# MAX14921_AFE.net
KiCad netlist of a schematic drawn in Altium Designer
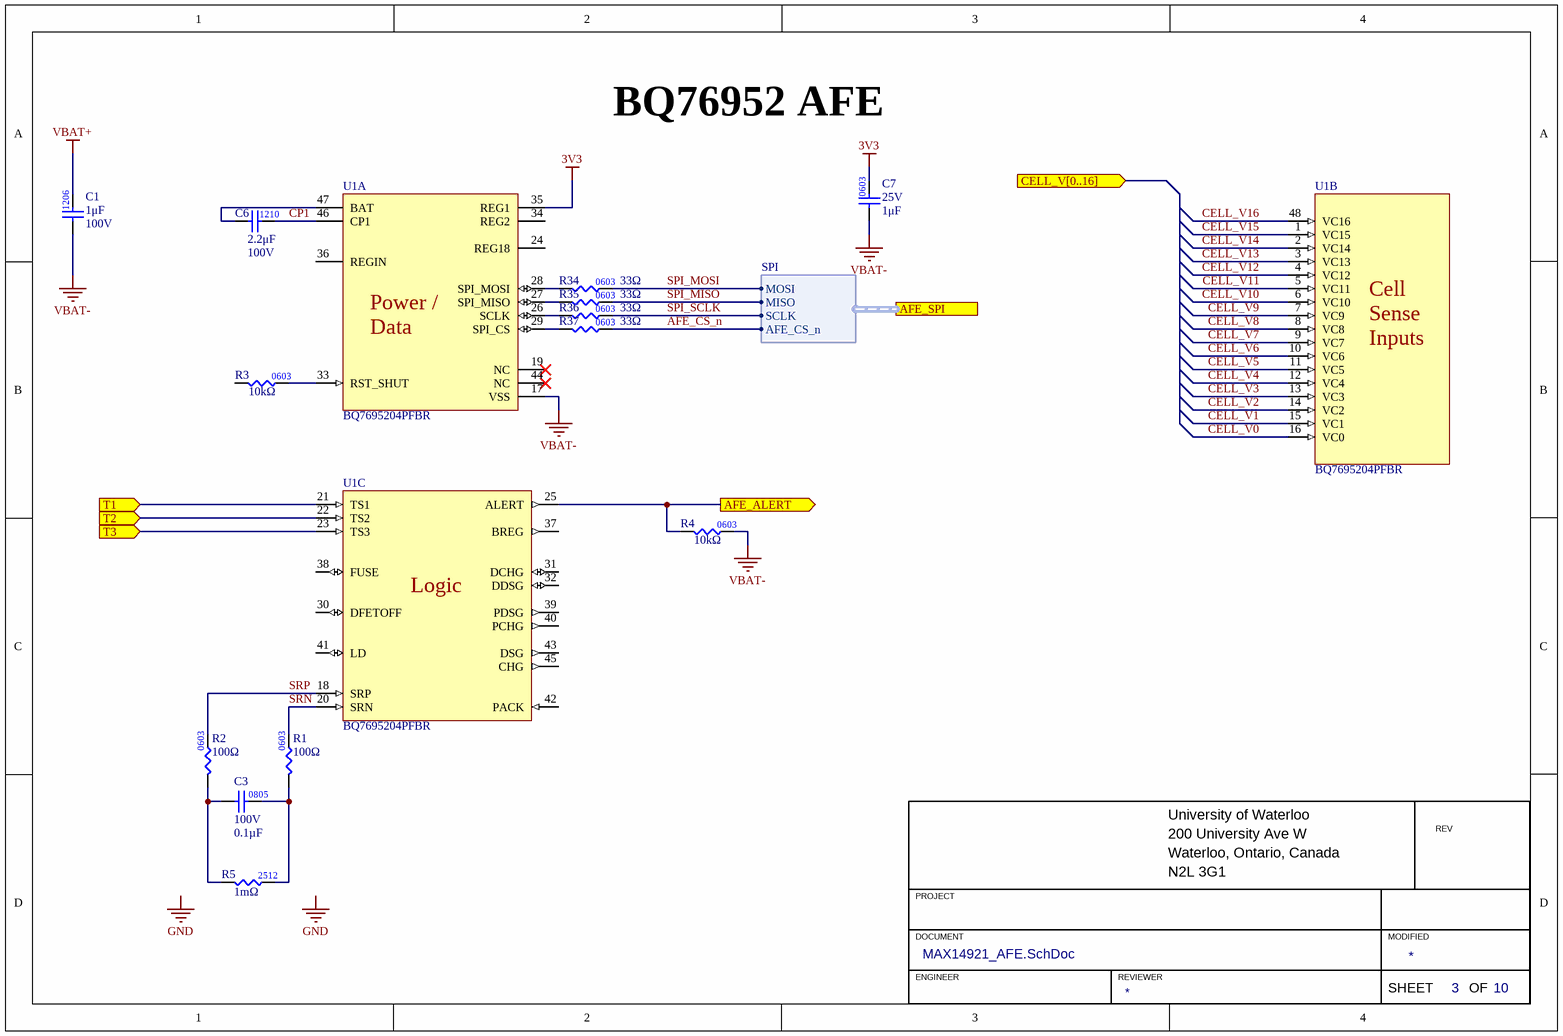
[diagram p0: MAX14921_AFE.SchDoc]

(export (version "E")
  (design (tool "Eeschema 10.0.6"))
  (components
    (comp (ref "C1")
      (value "1μF")
      (footprint "CAP1206")
      (description "CAP CER 1UF 100V X7R 1206")
      (fields (field (name "VOLTAGE RATING") "100V") (field (name "Comment") "CAP_1uF_100V_1206"))
      (libsource (lib "Personal_Schematic_Library_2022") (part "CAP_1uF_100V_1206"))
    )
    (comp (ref "C3")
      (value "0.1µF")
      (footprint "CAP0805")
      (description "CAP CER 0.1UF 100V X7R 0805")
      (fields (field (name "VOLTAGE RATING") "100V") (field (name "Comment") "CAP_0.1uF_100V_0805"))
      (libsource (lib "Personal_Schematic_Library_2022") (part "CAP_0.1uF_100V_0805"))
    )
    (comp (ref "C6")
      (value "2.2μF")
      (footprint "CAP1210")
      (description "CAP CER 2.2UF 100V X7R 1210")
      (fields (field (name "VOLTAGE RATING") "100V") (field (name "Comment") "CAP_2.2uF_100V_1210"))
      (libsource (lib "Personal_Schematic_Library_2022") (part "CAP_2.2uF_100V_1210"))
    )
    (comp (ref "C7")
      (value "1μF")
      (footprint "CAP0603")
      (description "CAP CER 1UF 25V X5R 0603")
      (fields (field (name "VOLTAGE RATING") "25V") (field (name "Comment") "CAP_1uF_25V_0603"))
      (libsource (lib "Personal_Schematic_Library_2022") (part "CAP_1uF_25V_0603"))
    )
    (comp (ref "R1")
      (value "100Ω")
      (footprint "RES0603")
      (description "RES 100 OHM 1% 1/10W 0603")
      (fields (field (name "Comment") "RES_100Ω_0603_1%"))
      (libsource (lib "Personal_Schematic_Library_2022") (part "RES_100Ω_0603_1%"))
    )
    (comp (ref "R2")
      (value "100Ω")
      (footprint "RES0603")
      (description "RES 100 OHM 1% 1/10W 0603")
      (fields (field (name "Comment") "RES_100Ω_0603_1%"))
      (libsource (lib "Personal_Schematic_Library_2022") (part "RES_100Ω_0603_1%"))
    )
    (comp (ref "R3")
      (value "10kΩ")
      (footprint "RES0603")
      (description "RES 10K OHM 1% 1/8W 0603")
      (fields (field (name "Comment") "RES_10kΩ_0603_1%"))
      (libsource (lib "Personal_Schematic_Library_2022") (part "RES_10kΩ_0603_1%"))
    )
    (comp (ref "R4")
      (value "10kΩ")
      (footprint "RES0603")
      (description "RES 10K OHM 1% 1/8W 0603")
      (fields (field (name "Comment") "RES_10kΩ_0603_1%"))
      (libsource (lib "Personal_Schematic_Library_2022") (part "RES_10kΩ_0603_1%"))
    )
    (comp (ref "R5")
      (value "1mΩ")
      (footprint "RESC6532X75N")
      (description "RES 1 mOHM 1% 3W 2512")
      (fields (field (name "Comment") "RES_1mΩ_2512_1%"))
      (libsource (lib "Personal_Schematic_Library_2022") (part "RES_1mΩ_2512_1%"))
    )
    (comp (ref "R34")
      (value "33Ω")
      (footprint "RES0603")
      (description "RES 33 OHM 1% 1/10W 0603")
      (fields (field (name "Comment") "RES_33Ω_0603_1%"))
      (libsource (lib "Personal_Schematic_Library_2022") (part "RES_33Ω_0603_1%"))
    )
    (comp (ref "R35")
      (value "33Ω")
      (footprint "RES0603")
      (description "RES 33 OHM 1% 1/10W 0603")
      (fields (field (name "Comment") "RES_33Ω_0603_1%"))
      (libsource (lib "Personal_Schematic_Library_2022") (part "RES_33Ω_0603_1%"))
    )
    (comp (ref "R36")
      (value "33Ω")
      (footprint "RES0603")
      (description "RES 33 OHM 1% 1/10W 0603")
      (fields (field (name "Comment") "RES_33Ω_0603_1%"))
      (libsource (lib "Personal_Schematic_Library_2022") (part "RES_33Ω_0603_1%"))
    )
    (comp (ref "R37")
      (value "33Ω")
      (footprint "RES0603")
      (description "RES 33 OHM 1% 1/10W 0603")
      (fields (field (name "Comment") "RES_33Ω_0603_1%"))
      (libsource (lib "Personal_Schematic_Library_2022") (part "RES_33Ω_0603_1%"))
    )
    (comp (ref "U1")
      (value "BQ7695204PFBR")
      (footprint "TI_48-TQFP")
      (description "IC BAT LIFEPO4/LI-ION 3-16C TQFP")
      (libsource (lib "Personal_Schematic_Library_2022") (part "BQ7695204PFBR"))
    )
  )
  (nets
    (net (code "2") (name "/AFE_ALERT") (class "Default")
      (node (ref "R4") (pin "1") (pinfunction "1_1") (pintype "passive"))
      (node (ref "U1") (pin "25") (pinfunction "ALERT_25") (pintype "output"))
    )
    (net (code "3") (name "/AFE_CS_n") (class "Default")
      (node (ref "R37") (pin "2") (pinfunction "2_2") (pintype "passive"))
    )
    (net (code "4") (name "/CELL_V0") (class "Default")
      (node (ref "U1") (pin "16") (pinfunction "VC0_16") (pintype "input"))
    )
    (net (code "5") (name "/CELL_V1") (class "Default")
      (node (ref "U1") (pin "15") (pinfunction "VC1_15") (pintype "input"))
    )
    (net (code "6") (name "/CELL_V2") (class "Default")
      (node (ref "U1") (pin "14") (pinfunction "VC2_14") (pintype "input"))
    )
    (net (code "7") (name "/CELL_V3") (class "Default")
      (node (ref "U1") (pin "13") (pinfunction "VC3_13") (pintype "input"))
    )
    (net (code "8") (name "/CELL_V4") (class "Default")
      (node (ref "U1") (pin "12") (pinfunction "VC4_12") (pintype "input"))
    )
    (net (code "9") (name "/CELL_V5") (class "Default")
      (node (ref "U1") (pin "11") (pinfunction "VC5_11") (pintype "input"))
    )
    (net (code "10") (name "/CELL_V6") (class "Default")
      (node (ref "U1") (pin "10") (pinfunction "VC6_10") (pintype "input"))
    )
    (net (code "11") (name "/CELL_V7") (class "Default")
      (node (ref "U1") (pin "9") (pinfunction "VC7_9") (pintype "input"))
    )
    (net (code "12") (name "/CELL_V8") (class "Default")
      (node (ref "U1") (pin "8") (pinfunction "VC8_8") (pintype "input"))
    )
    (net (code "13") (name "/CELL_V9") (class "Default")
      (node (ref "U1") (pin "7") (pinfunction "VC9_7") (pintype "input"))
    )
    (net (code "14") (name "/CELL_V10") (class "Default")
      (node (ref "U1") (pin "6") (pinfunction "VC10_6") (pintype "input"))
    )
    (net (code "15") (name "/CELL_V11") (class "Default")
      (node (ref "U1") (pin "5") (pinfunction "VC11_5") (pintype "input"))
    )
    (net (code "16") (name "/CELL_V12") (class "Default")
      (node (ref "U1") (pin "4") (pinfunction "VC12_4") (pintype "input"))
    )
    (net (code "17") (name "/CELL_V13") (class "Default")
      (node (ref "U1") (pin "3") (pinfunction "VC13_3") (pintype "input"))
    )
    (net (code "18") (name "/CELL_V14") (class "Default")
      (node (ref "U1") (pin "2") (pinfunction "VC14_2") (pintype "input"))
    )
    (net (code "19") (name "/CELL_V15") (class "Default")
      (node (ref "U1") (pin "1") (pinfunction "VC15_1") (pintype "input"))
    )
    (net (code "20") (name "/CELL_V16") (class "Default")
      (node (ref "U1") (pin "48") (pinfunction "VC16_48") (pintype "input"))
    )
    (net (code "22") (name "/CP1") (class "Default")
      (node (ref "C6") (pin "2") (pinfunction "2_2") (pintype "passive"))
      (node (ref "U1") (pin "46") (pinfunction "CP1_46") (pintype "power_in"))
    )
    (net (code "23") (name "/SPI_MISO") (class "Default")
      (node (ref "R35") (pin "2") (pinfunction "2_2") (pintype "passive"))
    )
    (net (code "24") (name "/SPI_MOSI") (class "Default")
      (node (ref "R34") (pin "2") (pinfunction "2_2") (pintype "passive"))
    )
    (net (code "25") (name "/SPI_SCLK") (class "Default")
      (node (ref "R36") (pin "2") (pinfunction "2_2") (pintype "passive"))
    )
    (net (code "26") (name "/SRN") (class "Default")
      (node (ref "R1") (pin "2") (pinfunction "2_2") (pintype "passive"))
      (node (ref "U1") (pin "20") (pinfunction "SRN_20") (pintype "input"))
    )
    (net (code "27") (name "/SRP") (class "Default")
      (node (ref "R2") (pin "2") (pinfunction "2_2") (pintype "passive"))
      (node (ref "U1") (pin "18") (pinfunction "SRP_18") (pintype "input"))
    )
    (net (code "28") (name "/T1") (class "Default")
      (node (ref "U1") (pin "21") (pinfunction "TS1_21") (pintype "input"))
    )
    (net (code "29") (name "/T2") (class "Default")
      (node (ref "U1") (pin "22") (pinfunction "TS2_22") (pintype "input"))
    )
    (net (code "30") (name "/T3") (class "Default")
      (node (ref "U1") (pin "23") (pinfunction "TS3_23") (pintype "input"))
    )
    (net (code "32") (name "3V3") (class "Default")
      (node (ref "C7") (pin "2") (pinfunction "2_2") (pintype "passive"))
      (node (ref "U1") (pin "35") (pinfunction "REG1_35") (pintype "power_in"))
    )
    (net (code "34") (name "Net-(C3-Pad1)") (class "Default")
      (node (ref "C3") (pin "1") (pinfunction "1_1") (pintype "passive"))
      (node (ref "R2") (pin "1") (pinfunction "1_1") (pintype "passive"))
      (node (ref "R5") (pin "1") (pinfunction "1_1") (pintype "passive"))
    )
    (net (code "35") (name "Net-(C3-Pad2)") (class "Default")
      (node (ref "C3") (pin "2") (pinfunction "2_2") (pintype "passive"))
      (node (ref "R1") (pin "1") (pinfunction "1_1") (pintype "passive"))
      (node (ref "R5") (pin "2") (pinfunction "2_2") (pintype "passive"))
    )
    (net (code "36") (name "Net-(U1A-BAT)") (class "Default")
      (node (ref "C6") (pin "1") (pinfunction "1_1") (pintype "passive"))
      (node (ref "U1") (pin "47") (pinfunction "BAT_47") (pintype "power_in"))
    )
    (net (code "37") (name "Net-(U1A-RST_SHUT)") (class "Default")
      (node (ref "R3") (pin "2") (pinfunction "2_2") (pintype "passive"))
      (node (ref "U1") (pin "33") (pinfunction "RST_SHUT_33") (pintype "input"))
    )
    (net (code "38") (name "Net-(U1A-SCLK)") (class "Default")
      (node (ref "R36") (pin "1") (pinfunction "1_1") (pintype "passive"))
      (node (ref "U1") (pin "26") (pinfunction "SCLK_26") (pintype "bidirectional"))
    )
    (net (code "39") (name "Net-(U1A-SPI_CS)") (class "Default")
      (node (ref "R37") (pin "1") (pinfunction "1_1") (pintype "passive"))
      (node (ref "U1") (pin "29") (pinfunction "SPI_CS_29") (pintype "bidirectional"))
    )
    (net (code "40") (name "Net-(U1A-SPI_MISO)") (class "Default")
      (node (ref "R35") (pin "1") (pinfunction "1_1") (pintype "passive"))
      (node (ref "U1") (pin "27") (pinfunction "SPI_MISO_27") (pintype "bidirectional"))
    )
    (net (code "41") (name "Net-(U1A-SPI_MOSI)") (class "Default")
      (node (ref "R34") (pin "1") (pinfunction "1_1") (pintype "passive"))
      (node (ref "U1") (pin "28") (pinfunction "SPI_MOSI_28") (pintype "bidirectional"))
    )
    (net (code "42") (name "VBAT+") (class "Default")
      (node (ref "C1") (pin "2") (pinfunction "2_2") (pintype "passive"))
    )
    (net (code "43") (name "VBAT-") (class "Default")
      (node (ref "C1") (pin "1") (pinfunction "1_1") (pintype "passive"))
      (node (ref "C7") (pin "1") (pinfunction "1_1") (pintype "passive"))
      (node (ref "R4") (pin "2") (pinfunction "2_2") (pintype "passive"))
      (node (ref "U1") (pin "17") (pinfunction "VSS_17") (pintype "power_in"))
    )
    (net (code "44") (name "unconnected-(R3-Pad1)") (class "Default")
      (node (ref "R3") (pin "1") (pinfunction "1_1") (pintype "passive"))
    )
    (net (code "45") (name "unconnected-(U1A-NC-Pad19)") (class "Default")
      (node (ref "U1") (pin "19") (pinfunction "NC_19") (pintype "passive+no_connect"))
    )
    (net (code "46") (name "unconnected-(U1A-NC-Pad44)") (class "Default")
      (node (ref "U1") (pin "44") (pinfunction "NC_44") (pintype "passive+no_connect"))
    )
    (net (code "47") (name "unconnected-(U1A-REG2-Pad34)") (class "Default")
      (node (ref "U1") (pin "34") (pinfunction "REG2_34") (pintype "power_in"))
    )
    (net (code "48") (name "unconnected-(U1A-REG18-Pad24)") (class "Default")
      (node (ref "U1") (pin "24") (pinfunction "REG18_24") (pintype "power_in"))
    )
    (net (code "49") (name "unconnected-(U1A-REGIN-Pad36)") (class "Default")
      (node (ref "U1") (pin "36") (pinfunction "REGIN_36") (pintype "power_in"))
    )
    (net (code "50") (name "unconnected-(U1C-BREG-Pad37)") (class "Default")
      (node (ref "U1") (pin "37") (pinfunction "BREG_37") (pintype "output"))
    )
    (net (code "51") (name "unconnected-(U1C-CHG-Pad45)") (class "Default")
      (node (ref "U1") (pin "45") (pinfunction "CHG_45") (pintype "output"))
    )
    (net (code "52") (name "unconnected-(U1C-DCHG-Pad31)") (class "Default")
      (node (ref "U1") (pin "31") (pinfunction "DCHG_31") (pintype "bidirectional"))
    )
    (net (code "53") (name "unconnected-(U1C-DDSG-Pad32)") (class "Default")
      (node (ref "U1") (pin "32") (pinfunction "DDSG_32") (pintype "bidirectional"))
    )
    (net (code "54") (name "unconnected-(U1C-DFETOFF-Pad30)") (class "Default")
      (node (ref "U1") (pin "30") (pinfunction "DFETOFF_30") (pintype "bidirectional"))
    )
    (net (code "55") (name "unconnected-(U1C-DSG-Pad43)") (class "Default")
      (node (ref "U1") (pin "43") (pinfunction "DSG_43") (pintype "output"))
    )
    (net (code "56") (name "unconnected-(U1C-FUSE-Pad38)") (class "Default")
      (node (ref "U1") (pin "38") (pinfunction "FUSE_38") (pintype "bidirectional"))
    )
    (net (code "57") (name "unconnected-(U1C-LD-Pad41)") (class "Default")
      (node (ref "U1") (pin "41") (pinfunction "LD_41") (pintype "bidirectional"))
    )
    (net (code "58") (name "unconnected-(U1C-PACK-Pad42)") (class "Default")
      (node (ref "U1") (pin "42") (pinfunction "PACK_42") (pintype "input"))
    )
    (net (code "59") (name "unconnected-(U1C-PCHG-Pad40)") (class "Default")
      (node (ref "U1") (pin "40") (pinfunction "PCHG_40") (pintype "output"))
    )
    (net (code "60") (name "unconnected-(U1C-PDSG-Pad39)") (class "Default")
      (node (ref "U1") (pin "39") (pinfunction "PDSG_39") (pintype "output"))
    )
  )
)
